# January.net
KiCad netlist of a schematic drawn in EAGLE
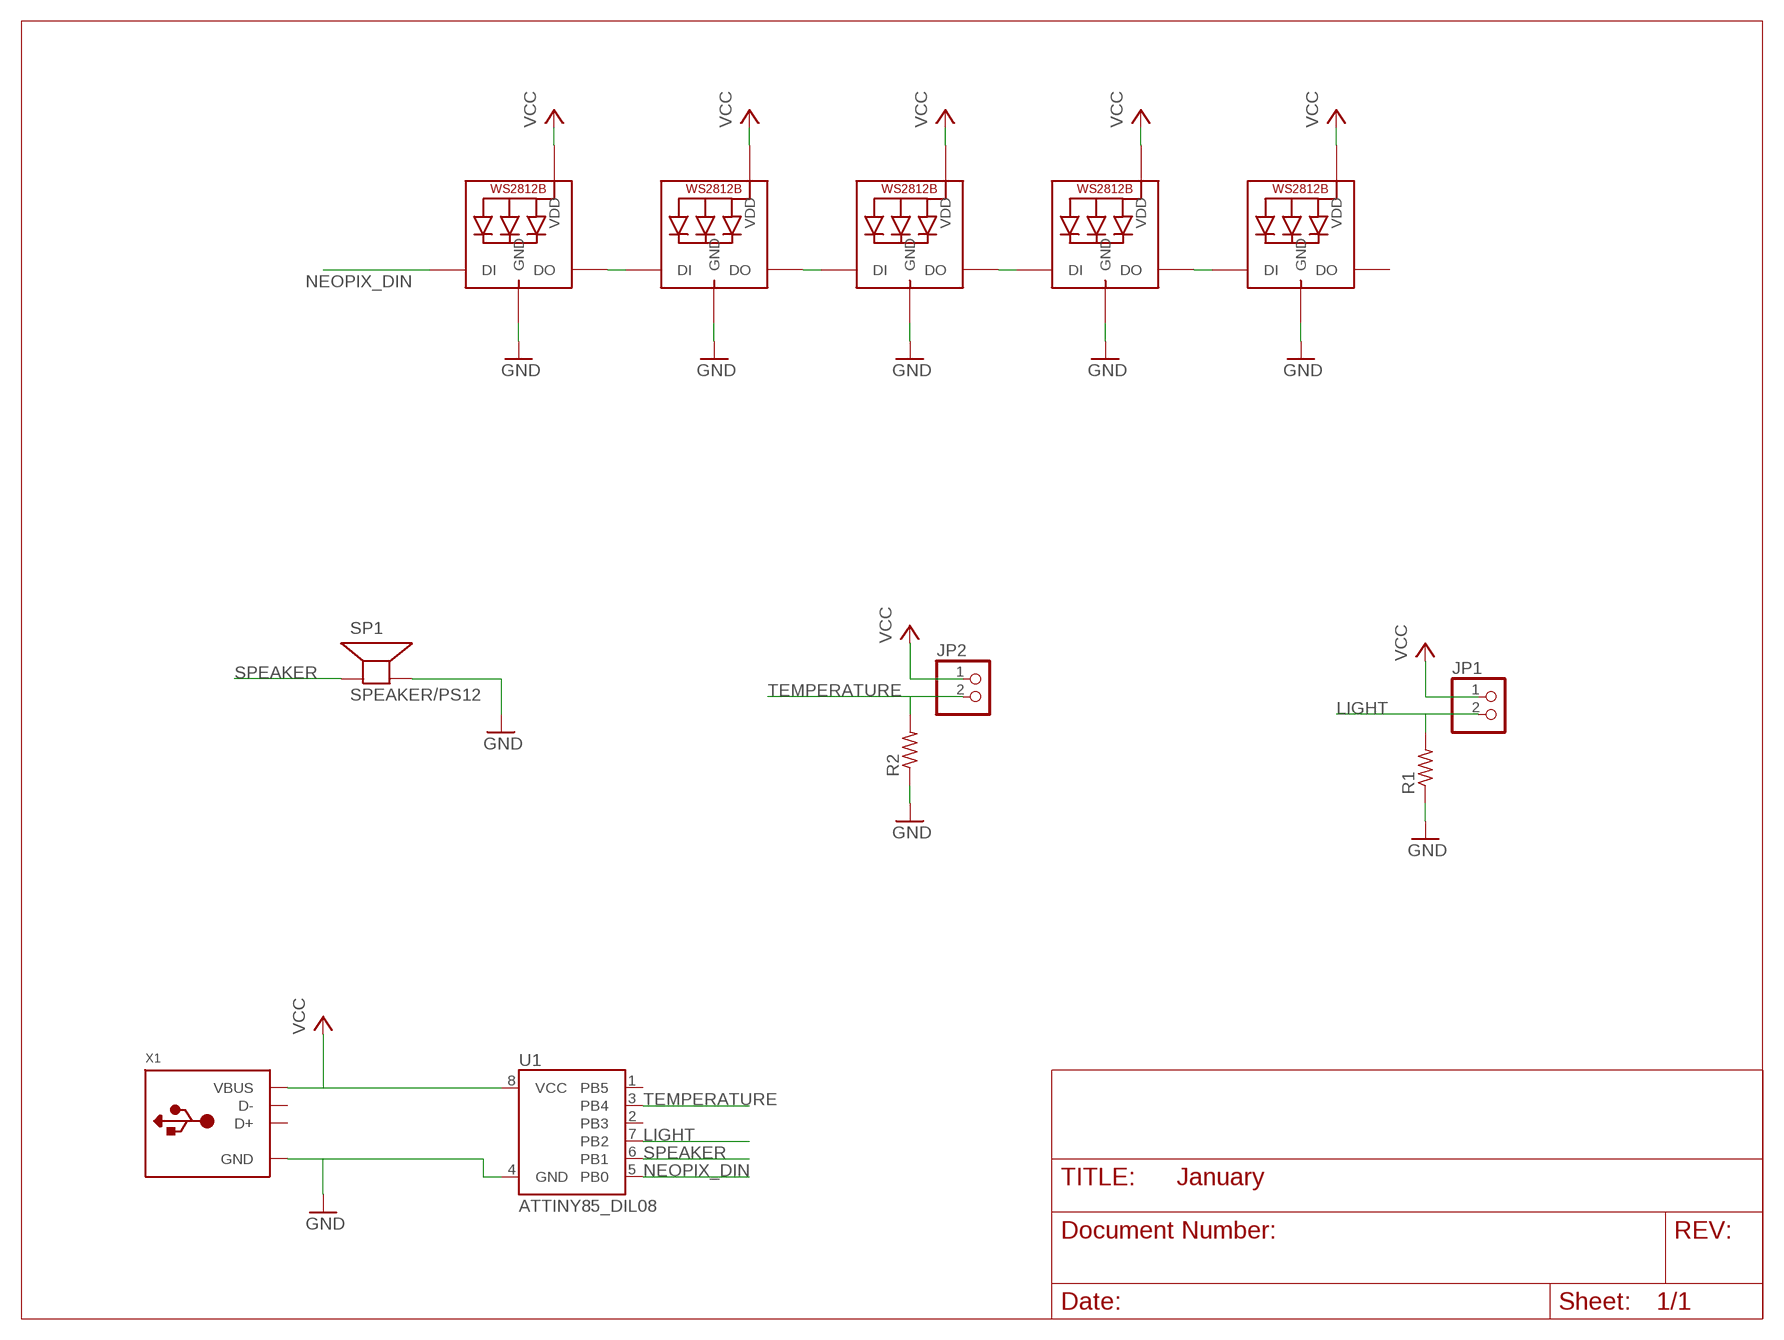
[diagram p0: schematic, sheet 1]

(export (version "E")
  (design (tool "Eeschema 10.0.6"))
  (components
    (comp (ref "JP1")
      (value "PINHD-1X2")
      (footprint "eagle-import:1X02")
      (libsource (lib "eagle-import") (part "PINHD-1X2"))
    )
    (comp (ref "JP2")
      (value "PINHD-1X2")
      (footprint "eagle-import:1X02")
      (libsource (lib "eagle-import") (part "PINHD-1X2"))
    )
    (comp (ref "NEO0")
      (value "NEOPIXEL_5MM")
      (footprint "eagle-import:LED5MM_4PIN")
      (libsource (lib "eagle-import") (part "NEOPIXEL_5MM"))
    )
    (comp (ref "NEO1")
      (value "NEOPIXEL_5MM")
      (footprint "eagle-import:LED5MM_4PIN")
      (libsource (lib "eagle-import") (part "NEOPIXEL_5MM"))
    )
    (comp (ref "NEO2")
      (value "NEOPIXEL_5MM")
      (footprint "eagle-import:LED5MM_4PIN")
      (libsource (lib "eagle-import") (part "NEOPIXEL_5MM"))
    )
    (comp (ref "NEO3")
      (value "NEOPIXEL_5MM")
      (footprint "eagle-import:LED5MM_4PIN")
      (libsource (lib "eagle-import") (part "NEOPIXEL_5MM"))
    )
    (comp (ref "NEO4")
      (value "NEOPIXEL_5MM")
      (footprint "eagle-import:LED5MM_4PIN")
      (libsource (lib "eagle-import") (part "NEOPIXEL_5MM"))
    )
    (comp (ref "R1")
      (value "R-US_0207/10")
      (footprint "eagle-import:0207_10")
      (libsource (lib "eagle-import") (part "R-US_0207/10"))
    )
    (comp (ref "R2")
      (value "R-US_0207/10")
      (footprint "eagle-import:0207_10")
      (libsource (lib "eagle-import") (part "R-US_0207/10"))
    )
    (comp (ref "SP1")
      (value "SPEAKER/PS12")
      (footprint "eagle-import:PS12")
      (libsource (lib "eagle-import") (part "SPEAKER/PS12"))
    )
    (comp (ref "U1")
      (value "ATTINY85_DIL08")
      (footprint "eagle-import:DIL08")
      (libsource (lib "eagle-import") (part "ATTINY85_DIL08"))
    )
    (comp (ref "X1")
      (value "MICROBUILDER_USB_TYPEAPCB")
      (footprint "eagle-import:MICROBUILDER_USBA_PCB")
      (libsource (lib "eagle-import") (part "MICROBUILDER_USB_TYPEAPCB"))
    )
  )
  (nets
    (net (code "1") (name "/LIGHT") (class "Default")
      (node (ref "JP1") (pin "2") (pinfunction "2_2") (pintype "passive"))
      (node (ref "R1") (pin "2") (pinfunction "2_2") (pintype "passive"))
      (node (ref "U1") (pin "7") (pinfunction "PB2_7") (pintype "bidirectional"))
    )
    (net (code "2") (name "/NEOPIX_DIN") (class "Default")
      (node (ref "NEO0") (pin "DI") (pinfunction "DI_DI") (pintype "input"))
      (node (ref "U1") (pin "5") (pinfunction "PB0_5") (pintype "bidirectional"))
    )
    (net (code "3") (name "/SPEAKER") (class "Default")
      (node (ref "SP1") (pin "P$1") (pinfunction "+_P$1") (pintype "passive"))
      (node (ref "U1") (pin "6") (pinfunction "PB1_6") (pintype "bidirectional"))
    )
    (net (code "4") (name "/TEMPERATURE") (class "Default")
      (node (ref "JP2") (pin "2") (pinfunction "2_2") (pintype "passive"))
      (node (ref "R2") (pin "2") (pinfunction "2_2") (pintype "passive"))
      (node (ref "U1") (pin "3") (pinfunction "PB4_3") (pintype "bidirectional"))
    )
    (net (code "5") (name "GND") (class "Default")
      (node (ref "NEO0") (pin "G") (pinfunction "GND_G") (pintype "power_in"))
      (node (ref "NEO1") (pin "G") (pinfunction "GND_G") (pintype "power_in"))
      (node (ref "NEO2") (pin "G") (pinfunction "GND_G") (pintype "power_in"))
      (node (ref "NEO3") (pin "G") (pinfunction "GND_G") (pintype "power_in"))
      (node (ref "NEO4") (pin "G") (pinfunction "GND_G") (pintype "power_in"))
      (node (ref "R1") (pin "1") (pinfunction "1_1") (pintype "passive"))
      (node (ref "R2") (pin "1") (pinfunction "1_1") (pintype "passive"))
      (node (ref "SP1") (pin "P$2") (pinfunction "-_P$2") (pintype "passive"))
      (node (ref "U1") (pin "4") (pinfunction "GND_4") (pintype "bidirectional"))
      (node (ref "X1") (pin "GND") (pinfunction "GND_GND") (pintype "power_in"))
    )
    (net (code "6") (name "Net-(NEO0-PadDO)") (class "Default")
      (node (ref "NEO0") (pin "DO") (pinfunction "DO_DO") (pintype "output"))
      (node (ref "NEO1") (pin "DI") (pinfunction "DI_DI") (pintype "input"))
    )
    (net (code "7") (name "Net-(NEO1-PadDO)") (class "Default")
      (node (ref "NEO1") (pin "DO") (pinfunction "DO_DO") (pintype "output"))
      (node (ref "NEO2") (pin "DI") (pinfunction "DI_DI") (pintype "input"))
    )
    (net (code "8") (name "Net-(NEO2-PadDO)") (class "Default")
      (node (ref "NEO2") (pin "DO") (pinfunction "DO_DO") (pintype "output"))
      (node (ref "NEO3") (pin "DI") (pinfunction "DI_DI") (pintype "input"))
    )
    (net (code "9") (name "Net-(NEO3-PadDO)") (class "Default")
      (node (ref "NEO3") (pin "DO") (pinfunction "DO_DO") (pintype "output"))
      (node (ref "NEO4") (pin "DI") (pinfunction "DI_DI") (pintype "input"))
    )
    (net (code "10") (name "VCC") (class "Default")
      (node (ref "JP1") (pin "1") (pinfunction "1_1") (pintype "passive"))
      (node (ref "JP2") (pin "1") (pinfunction "1_1") (pintype "passive"))
      (node (ref "NEO0") (pin "5V") (pinfunction "VDD_5V") (pintype "power_in"))
      (node (ref "NEO1") (pin "5V") (pinfunction "VDD_5V") (pintype "power_in"))
      (node (ref "NEO2") (pin "5V") (pinfunction "VDD_5V") (pintype "power_in"))
      (node (ref "NEO3") (pin "5V") (pinfunction "VDD_5V") (pintype "power_in"))
      (node (ref "NEO4") (pin "5V") (pinfunction "VDD_5V") (pintype "power_in"))
      (node (ref "U1") (pin "8") (pinfunction "VCC_8") (pintype "bidirectional"))
      (node (ref "X1") (pin "VCC") (pinfunction "VBUS_VCC") (pintype "power_in"))
    )
    (net (code "11") (name "unconnected-(NEO4-PadDO)") (class "Default")
      (node (ref "NEO4") (pin "DO") (pinfunction "DO_DO") (pintype "output"))
    )
    (net (code "12") (name "unconnected-(U1-PB3-Pad2)") (class "Default")
      (node (ref "U1") (pin "2") (pinfunction "PB3_2") (pintype "bidirectional"))
    )
    (net (code "13") (name "unconnected-(U1-PB5-Pad1)") (class "Default")
      (node (ref "U1") (pin "1") (pinfunction "PB5_1") (pintype "bidirectional"))
    )
    (net (code "14") (name "unconnected-(X1-D+-PadUSB_PLUS)") (class "Default")
      (node (ref "X1") (pin "USB_PLUS") (pinfunction "D+_USB_PLUS") (pintype "bidirectional"))
    )
    (net (code "15") (name "unconnected-(X1-D--PadUSB_NEG)") (class "Default")
      (node (ref "X1") (pin "USB_NEG") (pinfunction "D-_USB_NEG") (pintype "bidirectional"))
    )
  )
)
